# CAMERA_INTERFACE.net
KiCad netlist of a schematic drawn in Altium Designer
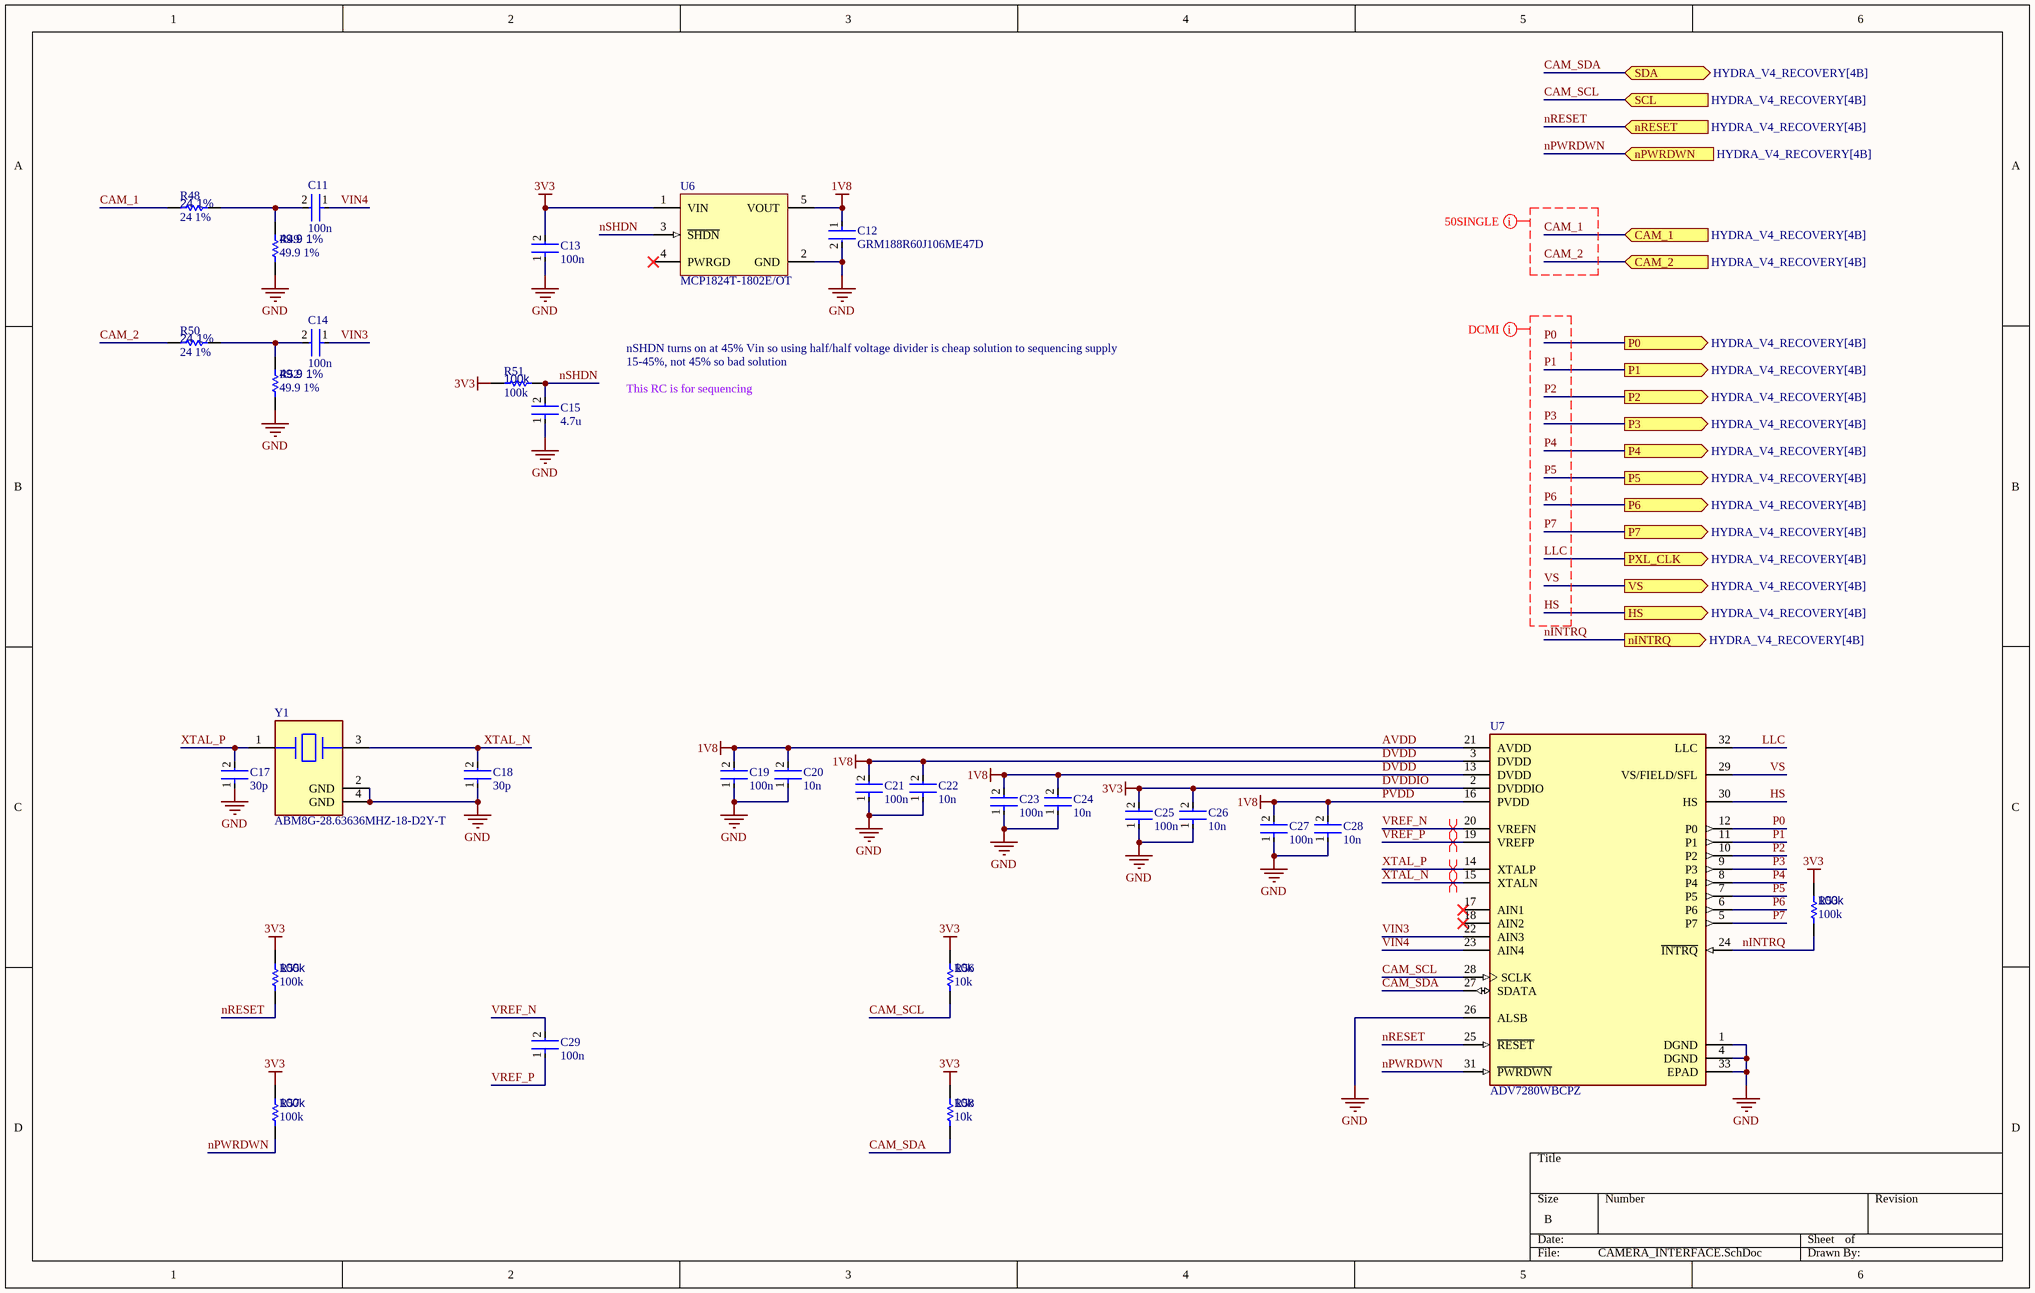
[diagram p0: CAMERA_INTERFACE.SchDoc]

(export (version "E")
  (design (tool "Eeschema 10.0.6"))
  (components
    (comp (ref "C11")
      (value "100n")
      (footprint "FP-0402-L_1_0_0_05-W_0_5-IPC_A")
      (description "LARGE PADS, 0402 CAP, CHANGE COMMENT TO MATCH REAL P/N")
      (libsource (lib "Space Concordia") (part "b4654b650e69147ec39a6b967a45e02"))
    )
    (comp (ref "C12")
      (value "GRM188R60J106ME47D")
      (footprint "FP-GRM188-0_1-e0_2_0_55-IPC_A")
      (description "Chip Multilayer Ceramic Capacitors for General Purpose, 0603, 10uF, X5R, 15%, 20%, 6.3V")
      (fields (field (name "VOLTAGE") "6.3V") (field (name "TOLERANCE") "20%"))
      (libsource (lib "Altium Content Vault") (part "02cd4be3c70576c341d710602a673aa"))
    )
    (comp (ref "C13")
      (value "100n")
      (footprint "FP-0402-L_1_0_0_05-W_0_5-IPC_A")
      (description "LARGE PADS, 0402 CAP, CHANGE COMMENT TO MATCH REAL P/N")
      (libsource (lib "Space Concordia") (part "b4654b650e69147ec39a6b967a45e02"))
    )
    (comp (ref "C14")
      (value "100n")
      (footprint "FP-0402-L_1_0_0_05-W_0_5-IPC_A")
      (description "LARGE PADS, 0402 CAP, CHANGE COMMENT TO MATCH REAL P/N")
      (libsource (lib "Space Concordia") (part "b4654b650e69147ec39a6b967a45e02"))
    )
    (comp (ref "C15")
      (value "4.7u")
      (footprint "FP-0402-L_1_0_0_05-W_0_5-IPC_A")
      (description "LARGE PADS, 0402 CAP, CHANGE COMMENT TO MATCH REAL P/N")
      (libsource (lib "Space Concordia") (part "b4654b650e69147ec39a6b967a45e02"))
    )
    (comp (ref "C17")
      (value "30p")
      (footprint "FP-0402-L_1_0_0_05-W_0_5-IPC_A")
      (description "LARGE PADS, 0402 CAP, CHANGE COMMENT TO MATCH REAL P/N")
      (libsource (lib "Space Concordia") (part "b4654b650e69147ec39a6b967a45e02"))
    )
    (comp (ref "C18")
      (value "30p")
      (footprint "FP-0402-L_1_0_0_05-W_0_5-IPC_A")
      (description "LARGE PADS, 0402 CAP, CHANGE COMMENT TO MATCH REAL P/N")
      (libsource (lib "Space Concordia") (part "b4654b650e69147ec39a6b967a45e02"))
    )
    (comp (ref "C19")
      (value "100n")
      (footprint "FP-0402-L_1_0_0_05-W_0_5-IPC_A")
      (description "LARGE PADS, 0402 CAP, CHANGE COMMENT TO MATCH REAL P/N")
      (libsource (lib "Space Concordia") (part "b4654b650e69147ec39a6b967a45e02"))
    )
    (comp (ref "C20")
      (value "10n")
      (footprint "FP-0402-L_1_0_0_05-W_0_5-IPC_A")
      (description "LARGE PADS, 0402 CAP, CHANGE COMMENT TO MATCH REAL P/N")
      (libsource (lib "Space Concordia") (part "b4654b650e69147ec39a6b967a45e02"))
    )
    (comp (ref "C21")
      (value "100n")
      (footprint "FP-0402-L_1_0_0_05-W_0_5-IPC_A")
      (description "LARGE PADS, 0402 CAP, CHANGE COMMENT TO MATCH REAL P/N")
      (libsource (lib "Space Concordia") (part "b4654b650e69147ec39a6b967a45e02"))
    )
    (comp (ref "C22")
      (value "10n")
      (footprint "FP-0402-L_1_0_0_05-W_0_5-IPC_A")
      (description "LARGE PADS, 0402 CAP, CHANGE COMMENT TO MATCH REAL P/N")
      (libsource (lib "Space Concordia") (part "b4654b650e69147ec39a6b967a45e02"))
    )
    (comp (ref "C23")
      (value "100n")
      (footprint "FP-0402-L_1_0_0_05-W_0_5-IPC_A")
      (description "LARGE PADS, 0402 CAP, CHANGE COMMENT TO MATCH REAL P/N")
      (libsource (lib "Space Concordia") (part "b4654b650e69147ec39a6b967a45e02"))
    )
    (comp (ref "C24")
      (value "10n")
      (footprint "FP-0402-L_1_0_0_05-W_0_5-IPC_A")
      (description "LARGE PADS, 0402 CAP, CHANGE COMMENT TO MATCH REAL P/N")
      (libsource (lib "Space Concordia") (part "b4654b650e69147ec39a6b967a45e02"))
    )
    (comp (ref "C25")
      (value "100n")
      (footprint "FP-0402-L_1_0_0_05-W_0_5-IPC_A")
      (description "LARGE PADS, 0402 CAP, CHANGE COMMENT TO MATCH REAL P/N")
      (libsource (lib "Space Concordia") (part "b4654b650e69147ec39a6b967a45e02"))
    )
    (comp (ref "C26")
      (value "10n")
      (footprint "FP-0402-L_1_0_0_05-W_0_5-IPC_A")
      (description "LARGE PADS, 0402 CAP, CHANGE COMMENT TO MATCH REAL P/N")
      (libsource (lib "Space Concordia") (part "b4654b650e69147ec39a6b967a45e02"))
    )
    (comp (ref "C27")
      (value "100n")
      (footprint "FP-0402-L_1_0_0_05-W_0_5-IPC_A")
      (description "LARGE PADS, 0402 CAP, CHANGE COMMENT TO MATCH REAL P/N")
      (libsource (lib "Space Concordia") (part "b4654b650e69147ec39a6b967a45e02"))
    )
    (comp (ref "C28")
      (value "10n")
      (footprint "FP-0402-L_1_0_0_05-W_0_5-IPC_A")
      (description "LARGE PADS, 0402 CAP, CHANGE COMMENT TO MATCH REAL P/N")
      (libsource (lib "Space Concordia") (part "b4654b650e69147ec39a6b967a45e02"))
    )
    (comp (ref "C29")
      (value "100n")
      (footprint "FP-0402-L_1_0_0_05-W_0_5-IPC_A")
      (description "LARGE PADS, 0402 CAP, CHANGE COMMENT TO MATCH REAL P/N")
      (libsource (lib "Space Concordia") (part "b4654b650e69147ec39a6b967a45e02"))
    )
    (comp (ref "R48")
      (value "24 1%")
      (footprint "R0603B")
      (description "Resistor")
      (fields (field (name "ALTIUM_VALUE") "24 1%"))
      (libsource (lib "Space Concordia") (part "Resistor"))
    )
    (comp (ref "R49")
      (value "49.9 1%")
      (footprint "R0603B")
      (description "Resistor")
      (fields (field (name "ALTIUM_VALUE") "49.9 1%"))
      (libsource (lib "Space Concordia") (part "Resistor"))
    )
    (comp (ref "R50")
      (value "24 1%")
      (footprint "R0603B")
      (description "Resistor")
      (fields (field (name "ALTIUM_VALUE") "24 1%"))
      (libsource (lib "Space Concordia") (part "Resistor"))
    )
    (comp (ref "R51")
      (value "100k")
      (footprint "R0603B")
      (description "Resistor")
      (fields (field (name "ALTIUM_VALUE") "100k"))
      (libsource (lib "Space Concordia") (part "Resistor"))
    )
    (comp (ref "R52")
      (value "49.9 1%")
      (footprint "R0603B")
      (description "Resistor")
      (fields (field (name "ALTIUM_VALUE") "49.9 1%"))
      (libsource (lib "Space Concordia") (part "Resistor"))
    )
    (comp (ref "R53")
      (value "100k")
      (footprint "R0603B")
      (description "Resistor")
      (fields (field (name "ALTIUM_VALUE") "100k"))
      (libsource (lib "Space Concordia") (part "Resistor"))
    )
    (comp (ref "R55")
      (value "100k")
      (footprint "R0603B")
      (description "Resistor")
      (fields (field (name "ALTIUM_VALUE") "100k"))
      (libsource (lib "Space Concordia") (part "Resistor"))
    )
    (comp (ref "R56")
      (value "10k")
      (footprint "R0603B")
      (description "Resistor")
      (fields (field (name "ALTIUM_VALUE") "10k"))
      (libsource (lib "Space Concordia") (part "Resistor"))
    )
    (comp (ref "R57")
      (value "100k")
      (footprint "R0603B")
      (description "Resistor")
      (fields (field (name "ALTIUM_VALUE") "100k"))
      (libsource (lib "Space Concordia") (part "Resistor"))
    )
    (comp (ref "R58")
      (value "10k")
      (footprint "R0603B")
      (description "Resistor")
      (fields (field (name "ALTIUM_VALUE") "10k"))
      (libsource (lib "Space Concordia") (part "Resistor"))
    )
    (comp (ref "U6")
      (value "MCP1824T-1802E/OT")
      (footprint "SOT-23-OT5_M")
      (libsource (lib "Altium Content Vault") (part "PM-LINEREG-MCP1824-IL5B"))
    )
    (comp (ref "U7")
      (value "ADV7280WBCPZ")
      (footprint "FP-CP-32-12-MFG")
      (description "Color Signal Decoder, CMOS")
      (libsource (lib "Space Concordia") (part "2e15c7328653806e765036f9cdadbb7"))
    )
    (comp (ref "Y1")
      (value "ABM8G-28.63636MHZ-18-D2Y-T")
      (footprint "FP-ABM8G-MFG")
      (description "Crystal 28.63636MHz ±20ppm (Tol) ±30ppm (Stability) 18pF FUND 50Ω 4-Pin SMD T/R")
      (fields (field (name "TOLERANCE") "20ppm"))
      (libsource (lib "Altium Content Vault") (part "48e526d86b7f2615d98721063c72f49"))
    )
  )
  (nets
    (net (code "1") (name "/CAM_1") (class "Default")
      (node (ref "R48") (pin "2") (pinfunction "2_2") (pintype "passive"))
    )
    (net (code "2") (name "/CAM_2") (class "Default")
      (node (ref "R50") (pin "2") (pinfunction "2_2") (pintype "passive"))
    )
    (net (code "3") (name "/CAM_SCL") (class "Default")
      (node (ref "R56") (pin "2") (pinfunction "2_2") (pintype "passive"))
      (node (ref "U7") (pin "28") (pinfunction "SCLK_28") (pintype "input"))
    )
    (net (code "4") (name "/CAM_SDA") (class "Default")
      (node (ref "R58") (pin "2") (pinfunction "2_2") (pintype "passive"))
      (node (ref "U7") (pin "27") (pinfunction "SDATA_27") (pintype "bidirectional"))
    )
    (net (code "5") (name "/HS") (class "Default")
      (node (ref "U7") (pin "30") (pinfunction "HS_30") (pintype "passive"))
    )
    (net (code "6") (name "/LLC") (class "Default")
      (node (ref "U7") (pin "32") (pinfunction "LLC_32") (pintype "passive"))
    )
    (net (code "7") (name "/P0") (class "Default")
      (node (ref "U7") (pin "12") (pinfunction "P0_12") (pintype "output"))
    )
    (net (code "8") (name "/P1") (class "Default")
      (node (ref "U7") (pin "11") (pinfunction "P1_11") (pintype "output"))
    )
    (net (code "9") (name "/P2") (class "Default")
      (node (ref "U7") (pin "10") (pinfunction "P2_10") (pintype "output"))
    )
    (net (code "10") (name "/P3") (class "Default")
      (node (ref "U7") (pin "9") (pinfunction "P3_9") (pintype "output"))
    )
    (net (code "11") (name "/P4") (class "Default")
      (node (ref "U7") (pin "8") (pinfunction "P4_8") (pintype "output"))
    )
    (net (code "12") (name "/P5") (class "Default")
      (node (ref "U7") (pin "7") (pinfunction "P5_7") (pintype "output"))
    )
    (net (code "13") (name "/P6") (class "Default")
      (node (ref "U7") (pin "6") (pinfunction "P6_6") (pintype "output"))
    )
    (net (code "14") (name "/P7") (class "Default")
      (node (ref "U7") (pin "5") (pinfunction "P7_5") (pintype "output"))
    )
    (net (code "15") (name "/VIN3") (class "Default")
      (node (ref "C14") (pin "1") (pinfunction "1_1") (pintype "passive"))
      (node (ref "U7") (pin "22") (pinfunction "AIN3_22") (pintype "passive"))
    )
    (net (code "16") (name "/VIN4") (class "Default")
      (node (ref "C11") (pin "1") (pinfunction "1_1") (pintype "passive"))
      (node (ref "U7") (pin "23") (pinfunction "AIN4_23") (pintype "passive"))
    )
    (net (code "17") (name "/VREF_N") (class "Default")
      (node (ref "C29") (pin "2") (pinfunction "2_2") (pintype "passive"))
      (node (ref "U7") (pin "20") (pinfunction "VREFN_20") (pintype "passive"))
    )
    (net (code "18") (name "/VREF_P") (class "Default")
      (node (ref "C29") (pin "1") (pinfunction "1_1") (pintype "passive"))
      (node (ref "U7") (pin "19") (pinfunction "VREFP_19") (pintype "passive"))
    )
    (net (code "19") (name "/VS") (class "Default")
      (node (ref "U7") (pin "29") (pinfunction "VS/FIELD/SFL_29") (pintype "passive"))
    )
    (net (code "20") (name "/XTAL_N") (class "Default")
      (node (ref "C18") (pin "2") (pinfunction "2_2") (pintype "passive"))
      (node (ref "U7") (pin "15") (pinfunction "XTALN_15") (pintype "passive"))
      (node (ref "Y1") (pin "3") (pinfunction "3_3") (pintype "passive"))
    )
    (net (code "21") (name "/XTAL_P") (class "Default")
      (node (ref "C17") (pin "2") (pinfunction "2_2") (pintype "passive"))
      (node (ref "U7") (pin "14") (pinfunction "XTALP_14") (pintype "passive"))
      (node (ref "Y1") (pin "1") (pinfunction "1_1") (pintype "passive"))
    )
    (net (code "22") (name "/nINTRQ") (class "Default")
      (node (ref "R53") (pin "2") (pinfunction "2_2") (pintype "passive"))
      (node (ref "U7") (pin "24") (pinfunction "~{INTRQ}_24") (pintype "input"))
    )
    (net (code "23") (name "/nPWRDWN") (class "Default")
      (node (ref "R57") (pin "2") (pinfunction "2_2") (pintype "passive"))
      (node (ref "U7") (pin "31") (pinfunction "~{PWRDWN}_31") (pintype "input"))
    )
    (net (code "24") (name "/nRESET") (class "Default")
      (node (ref "R55") (pin "2") (pinfunction "2_2") (pintype "passive"))
      (node (ref "U7") (pin "25") (pinfunction "~{RESET}_25") (pintype "input"))
    )
    (net (code "25") (name "/nSHDN") (class "Default")
      (node (ref "C15") (pin "2") (pinfunction "2_2") (pintype "passive"))
      (node (ref "R51") (pin "1") (pinfunction "1_1") (pintype "passive"))
      (node (ref "U6") (pin "3") (pinfunction "~{SHDN}_3") (pintype "input"))
    )
    (net (code "26") (name "1V8") (class "Default")
      (node (ref "C12") (pin "1") (pinfunction "1_1") (pintype "passive"))
      (node (ref "C19") (pin "2") (pinfunction "2_2") (pintype "passive"))
      (node (ref "C20") (pin "2") (pinfunction "2_2") (pintype "passive"))
      (node (ref "C21") (pin "2") (pinfunction "2_2") (pintype "passive"))
      (node (ref "C22") (pin "2") (pinfunction "2_2") (pintype "passive"))
      (node (ref "C23") (pin "2") (pinfunction "2_2") (pintype "passive"))
      (node (ref "C24") (pin "2") (pinfunction "2_2") (pintype "passive"))
      (node (ref "C27") (pin "2") (pinfunction "2_2") (pintype "passive"))
      (node (ref "C28") (pin "2") (pinfunction "2_2") (pintype "passive"))
      (node (ref "U6") (pin "5") (pinfunction "VOUT_5") (pintype "power_in"))
      (node (ref "U7") (pin "13") (pinfunction "DVDD_13") (pintype "power_in"))
      (node (ref "U7") (pin "16") (pinfunction "PVDD_16") (pintype "power_in"))
      (node (ref "U7") (pin "21") (pinfunction "AVDD_21") (pintype "power_in"))
      (node (ref "U7") (pin "3") (pinfunction "DVDD_3") (pintype "power_in"))
    )
    (net (code "27") (name "3V3") (class "Default")
      (node (ref "C13") (pin "2") (pinfunction "2_2") (pintype "passive"))
      (node (ref "C25") (pin "2") (pinfunction "2_2") (pintype "passive"))
      (node (ref "C26") (pin "2") (pinfunction "2_2") (pintype "passive"))
      (node (ref "R51") (pin "2") (pinfunction "2_2") (pintype "passive"))
      (node (ref "R53") (pin "1") (pinfunction "1_1") (pintype "passive"))
      (node (ref "R55") (pin "1") (pinfunction "1_1") (pintype "passive"))
      (node (ref "R56") (pin "1") (pinfunction "1_1") (pintype "passive"))
      (node (ref "R57") (pin "1") (pinfunction "1_1") (pintype "passive"))
      (node (ref "R58") (pin "1") (pinfunction "1_1") (pintype "passive"))
      (node (ref "U6") (pin "1") (pinfunction "VIN_1") (pintype "power_in"))
      (node (ref "U7") (pin "2") (pinfunction "DVDDIO_2") (pintype "power_in"))
    )
    (net (code "28") (name "GND") (class "Default")
      (node (ref "C12") (pin "2") (pinfunction "2_2") (pintype "passive"))
      (node (ref "C13") (pin "1") (pinfunction "1_1") (pintype "passive"))
      (node (ref "C15") (pin "1") (pinfunction "1_1") (pintype "passive"))
      (node (ref "C17") (pin "1") (pinfunction "1_1") (pintype "passive"))
      (node (ref "C18") (pin "1") (pinfunction "1_1") (pintype "passive"))
      (node (ref "C19") (pin "1") (pinfunction "1_1") (pintype "passive"))
      (node (ref "C20") (pin "1") (pinfunction "1_1") (pintype "passive"))
      (node (ref "C21") (pin "1") (pinfunction "1_1") (pintype "passive"))
      (node (ref "C22") (pin "1") (pinfunction "1_1") (pintype "passive"))
      (node (ref "C23") (pin "1") (pinfunction "1_1") (pintype "passive"))
      (node (ref "C24") (pin "1") (pinfunction "1_1") (pintype "passive"))
      (node (ref "C25") (pin "1") (pinfunction "1_1") (pintype "passive"))
      (node (ref "C26") (pin "1") (pinfunction "1_1") (pintype "passive"))
      (node (ref "C27") (pin "1") (pinfunction "1_1") (pintype "passive"))
      (node (ref "C28") (pin "1") (pinfunction "1_1") (pintype "passive"))
      (node (ref "R49") (pin "1") (pinfunction "1_1") (pintype "passive"))
      (node (ref "R52") (pin "1") (pinfunction "1_1") (pintype "passive"))
      (node (ref "U6") (pin "2") (pinfunction "GND_2") (pintype "power_in"))
      (node (ref "U7") (pin "1") (pinfunction "DGND_1") (pintype "power_in"))
      (node (ref "U7") (pin "26") (pinfunction "ALSB_26") (pintype "passive"))
      (node (ref "U7") (pin "33") (pinfunction "EPAD_33") (pintype "passive"))
      (node (ref "U7") (pin "4") (pinfunction "DGND_4") (pintype "power_in"))
      (node (ref "Y1") (pin "2") (pinfunction "GND_2") (pintype "power_in"))
      (node (ref "Y1") (pin "4") (pinfunction "GND_4") (pintype "power_in"))
    )
    (net (code "29") (name "Net-(C11-Pad2)") (class "Default")
      (node (ref "C11") (pin "2") (pinfunction "2_2") (pintype "passive"))
      (node (ref "R48") (pin "1") (pinfunction "1_1") (pintype "passive"))
      (node (ref "R49") (pin "2") (pinfunction "2_2") (pintype "passive"))
    )
    (net (code "30") (name "Net-(C14-Pad2)") (class "Default")
      (node (ref "C14") (pin "2") (pinfunction "2_2") (pintype "passive"))
      (node (ref "R50") (pin "1") (pinfunction "1_1") (pintype "passive"))
      (node (ref "R52") (pin "2") (pinfunction "2_2") (pintype "passive"))
    )
    (net (code "31") (name "unconnected-(U6-PWRGD-Pad4)") (class "Default")
      (node (ref "U6") (pin "4") (pinfunction "PWRGD_4") (pintype "power_in+no_connect"))
    )
    (net (code "32") (name "unconnected-(U7-AIN1-Pad17)") (class "Default")
      (node (ref "U7") (pin "17") (pinfunction "AIN1_17") (pintype "tri_state+no_connect"))
    )
    (net (code "33") (name "unconnected-(U7-AIN2-Pad18)") (class "Default")
      (node (ref "U7") (pin "18") (pinfunction "AIN2_18") (pintype "tri_state+no_connect"))
    )
  )
)
